# 202011AWSNP04.net
KiCad netlist of a schematic drawn in Altium Designer
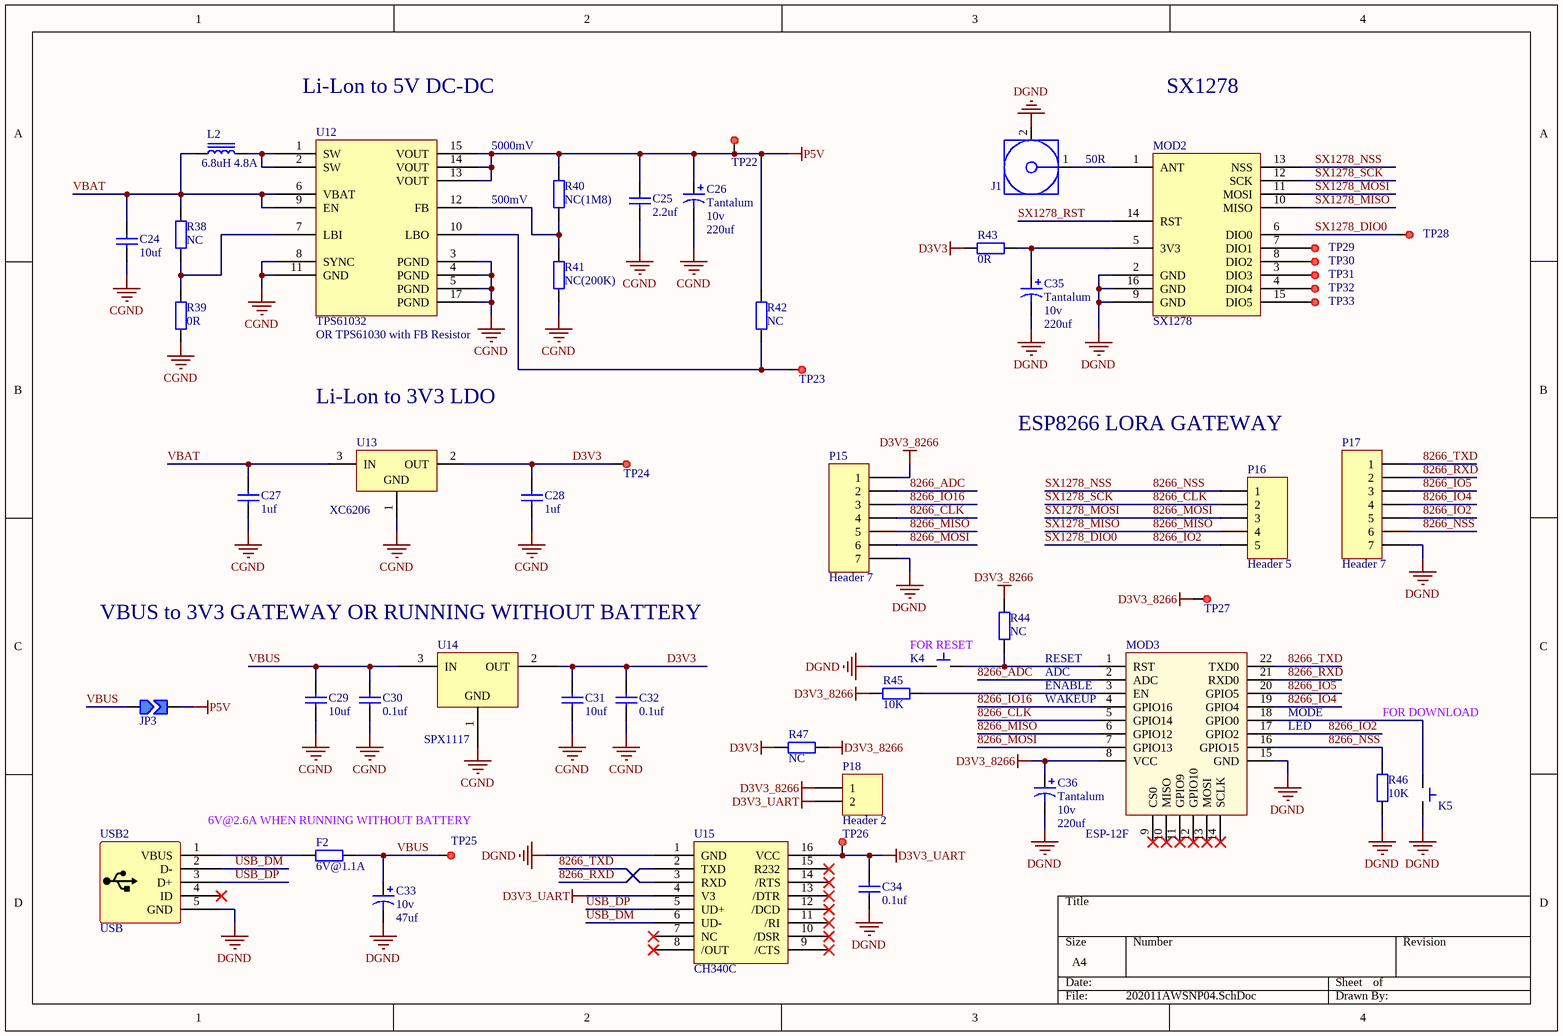
[diagram p0: 202011AWSNP04.SchDoc]

(export (version "E")
  (design (tool "Eeschema 10.0.6"))
  (components
    (comp (ref "C24")
      (value "10uf")
      (footprint "C0805")
      (fields (field (name "Comment") "Cap"))
      (libsource (lib "carrot_lib") (part "Cap"))
    )
    (comp (ref "C25")
      (value "2.2uf")
      (footprint "C0805")
      (fields (field (name "Comment") "Cap"))
      (libsource (lib "carrot_lib") (part "Cap"))
    )
    (comp (ref "C26")
      (value "Tantalum")
      (footprint "C2917T-7343D")
      (fields (field (name "VOLTAGE") "10v") (field (name "ALTIUM_VALUE") "220uf"))
      (libsource (lib "carrot_lib") (part "Cap-Tantalum"))
    )
    (comp (ref "C27")
      (value "1uf")
      (footprint "C0805")
      (fields (field (name "Comment") "Cap"))
      (libsource (lib "carrot_lib") (part "Cap"))
    )
    (comp (ref "C28")
      (value "1uf")
      (footprint "C0805")
      (fields (field (name "Comment") "Cap"))
      (libsource (lib "carrot_lib") (part "Cap"))
    )
    (comp (ref "C29")
      (value "10uf")
      (footprint "C0805")
      (fields (field (name "Comment") "Cap"))
      (libsource (lib "carrot_lib") (part "Cap"))
    )
    (comp (ref "C30")
      (value "0.1uf")
      (footprint "C0805")
      (fields (field (name "Comment") "Cap"))
      (libsource (lib "carrot_lib") (part "Cap"))
    )
    (comp (ref "C31")
      (value "10uf")
      (footprint "C0805")
      (fields (field (name "Comment") "Cap"))
      (libsource (lib "carrot_lib") (part "Cap"))
    )
    (comp (ref "C32")
      (value "0.1uf")
      (footprint "C0805")
      (fields (field (name "Comment") "Cap"))
      (libsource (lib "carrot_lib") (part "Cap"))
    )
    (comp (ref "C33")
      (value "47uf")
      (footprint "C4X5.4-SMD")
      (fields (field (name "VOLTAGE") "10v") (field (name "Comment") "Cap2"))
      (libsource (lib "carrot_lib") (part "Cap2"))
    )
    (comp (ref "C34")
      (value "0.1uf")
      (footprint "C0805")
      (fields (field (name "Comment") "Cap"))
      (libsource (lib "carrot_lib") (part "Cap"))
    )
    (comp (ref "C35")
      (value "Tantalum")
      (footprint "C2917T-7343D")
      (fields (field (name "VOLTAGE") "10v") (field (name "ALTIUM_VALUE") "220uf"))
      (libsource (lib "carrot_lib") (part "Cap-Tantalum"))
    )
    (comp (ref "C36")
      (value "Tantalum")
      (footprint "C2917T-7343D")
      (fields (field (name "VOLTAGE") "10v") (field (name "ALTIUM_VALUE") "220uf"))
      (libsource (lib "carrot_lib") (part "Cap-Tantalum"))
    )
    (comp (ref "F2")
      (value "6V@1.1A")
      (footprint "F1812")
      (fields (field (name "Comment") "Fuse"))
      (libsource (lib "carrot_lib") (part "Fuse"))
    )
    (comp (ref "J1") (value "SMA") (footprint "SMA-3") (libsource (lib "carrot_lib") (part "SMA")))
    (comp (ref "JP3") (value "Jumper") (footprint "Jumper-2") (libsource (lib "carrot_lib") (part "Jumper")))
    (comp (ref "K4")
      (value "Button")
      (footprint "Button-SMT-Small")
      (description "轻触开关")
      (libsource (lib "carrot_lib") (part "Button"))
    )
    (comp (ref "K5")
      (value "Button")
      (footprint "Button-SMT-Small")
      (description "轻触开关")
      (libsource (lib "carrot_lib") (part "Button"))
    )
    (comp (ref "L2")
      (value "6.8uH 4.8A")
      (footprint "L10104")
      (description "Magnetic-Core Inductor")
      (fields (field (name "Comment") "Inductor Iron"))
      (libsource (lib "carrot_lib") (part "Inductor Iron"))
    )
    (comp (ref "MOD2")
      (value "SX1278")
      (footprint "MODULE SX1278")
      (libsource (lib "carrot_lib") (part "Module SX1278"))
    )
    (comp (ref "MOD3")
      (value "ESP-12F")
      (footprint "MODULE ESP-12F")
      (libsource (lib "carrot_lib") (part "Module ESP-12F"))
    )
    (comp (ref "P15")
      (value "Header 7")
      (footprint "HDR1X7")
      (description "Header, 7-Pin")
      (fields (field (name "PUBLISHER") "Altium Limited"))
      (libsource (lib "Miscellaneous Connectors") (part "Header 7"))
    )
    (comp (ref "P16")
      (value "Header 5")
      (footprint "HDR1X5")
      (description "Header, 5-Pin")
      (fields (field (name "PUBLISHER") "Altium Limited"))
      (libsource (lib "Miscellaneous Connectors") (part "Header 5"))
    )
    (comp (ref "P17")
      (value "Header 7")
      (footprint "HDR1X7")
      (description "Header, 7-Pin")
      (fields (field (name "PUBLISHER") "Altium Limited"))
      (libsource (lib "Miscellaneous Connectors") (part "Header 7"))
    )
    (comp (ref "P18")
      (value "Header 2")
      (footprint "HDR1X2")
      (description "Header, 2-Pin")
      (fields (field (name "PUBLISHER") "Altium Limited"))
      (libsource (lib "Miscellaneous Connectors") (part "Header 2"))
    )
    (comp (ref "R38")
      (value "NC")
      (footprint "R0805")
      (description "电阻")
      (fields (field (name "Comment") "Res"))
      (libsource (lib "") (part "Res_3"))
    )
    (comp (ref "R39")
      (value "0R")
      (footprint "R0805")
      (description "电阻")
      (fields (field (name "Comment") "Res"))
      (libsource (lib "") (part "Res_3"))
    )
    (comp (ref "R40")
      (value "NC(1M8)")
      (footprint "R0805")
      (description "电阻")
      (fields (field (name "Comment") "Res"))
      (libsource (lib "") (part "Res_3"))
    )
    (comp (ref "R41")
      (value "NC(200K)")
      (footprint "R0805")
      (description "电阻")
      (fields (field (name "Comment") "Res"))
      (libsource (lib "") (part "Res_3"))
    )
    (comp (ref "R42")
      (value "NC")
      (footprint "R0805")
      (description "电阻")
      (fields (field (name "Comment") "Res"))
      (libsource (lib "") (part "Res_3"))
    )
    (comp (ref "R43")
      (value "0R")
      (footprint "R0805")
      (description "电阻")
      (fields (field (name "Comment") "Res"))
      (libsource (lib "") (part "Res_2"))
    )
    (comp (ref "R44")
      (value "NC")
      (footprint "R0805")
      (description "电阻")
      (fields (field (name "Comment") "Res"))
      (libsource (lib "") (part "Res_3"))
    )
    (comp (ref "R45")
      (value "10K")
      (footprint "R0805")
      (description "电阻")
      (fields (field (name "Comment") "Res"))
      (libsource (lib "") (part "Res_1"))
    )
    (comp (ref "R46")
      (value "10K")
      (footprint "R0805")
      (description "电阻")
      (fields (field (name "Comment") "Res"))
      (libsource (lib "carrot_lib") (part "Res"))
    )
    (comp (ref "R47")
      (value "NC")
      (footprint "R0805")
      (description "电阻")
      (fields (field (name "Comment") "Res"))
      (libsource (lib "") (part "Res_1"))
    )
    (comp (ref "TP22")
      (value "TestPoint")
      (footprint "TestPoint-R30")
      (description "测试点")
      (libsource (lib "carrot_lib") (part "TestPoint"))
    )
    (comp (ref "TP23")
      (value "TestPoint")
      (footprint "TestPoint-R30")
      (description "测试点")
      (libsource (lib "carrot_lib") (part "TestPoint"))
    )
    (comp (ref "TP24")
      (value "TestPoint")
      (footprint "TestPoint-R30")
      (description "测试点")
      (libsource (lib "carrot_lib") (part "TestPoint"))
    )
    (comp (ref "TP25")
      (value "TestPoint")
      (footprint "TestPoint-R30")
      (description "测试点")
      (libsource (lib "carrot_lib") (part "TestPoint"))
    )
    (comp (ref "TP26")
      (value "TestPoint")
      (footprint "TestPoint-R30")
      (description "测试点")
      (libsource (lib "carrot_lib") (part "TestPoint"))
    )
    (comp (ref "TP27")
      (value "TestPoint")
      (footprint "TestPoint-R30")
      (description "测试点")
      (libsource (lib "carrot_lib") (part "TestPoint"))
    )
    (comp (ref "TP28")
      (value "TestPoint")
      (footprint "TestPoint-R30")
      (description "测试点")
      (libsource (lib "carrot_lib") (part "TestPoint"))
    )
    (comp (ref "TP29")
      (value "TestPoint")
      (footprint "TestPoint-R30")
      (description "测试点")
      (libsource (lib "carrot_lib") (part "TestPoint"))
    )
    (comp (ref "TP30")
      (value "TestPoint")
      (footprint "TestPoint-R30")
      (description "测试点")
      (libsource (lib "carrot_lib") (part "TestPoint"))
    )
    (comp (ref "TP31")
      (value "TestPoint")
      (footprint "TestPoint-R30")
      (description "测试点")
      (libsource (lib "carrot_lib") (part "TestPoint"))
    )
    (comp (ref "TP32")
      (value "TestPoint")
      (footprint "TestPoint-R30")
      (description "测试点")
      (libsource (lib "carrot_lib") (part "TestPoint"))
    )
    (comp (ref "TP33")
      (value "TestPoint")
      (footprint "TestPoint-R30")
      (description "测试点")
      (libsource (lib "carrot_lib") (part "TestPoint"))
    )
    (comp (ref "U12")
      (value "TPS61032")
      (footprint "TPS61030-TSSOP16")
      (description "TPS6103x 96% Efficient Synchronous Boost Converter With 4A Switch")
      (libsource (lib "carrot_lib") (part "TPS61032PWP"))
    )
    (comp (ref "U13")
      (value "XC6206")
      (footprint "XC6206-SOT23")
      (description "Low ESR Cap. Compatible Positive Voltage Regulators")
      (libsource (lib "carrot_lib") (part "XC6206"))
    )
    (comp (ref "U14")
      (value "SPX1117")
      (footprint "SPX1117-SOT223")
      (description "800mA Low Dropout Voltage Regulator")
      (libsource (lib "carrot_lib") (part "SPX1117"))
    )
    (comp (ref "U15")
      (value "CH340C")
      (footprint "CH340C-SOP16")
      (description "USB 转串口芯片")
      (libsource (lib "carrot_lib") (part "CH340C"))
    )
    (comp (ref "USB2") (value "USB") (footprint "USB-Mini-SMT") (libsource (lib "carrot_lib") (part "USB")))
  )
  (nets
    (net (code "1") (name "/8266_ADC") (class "Default")
      (node (ref "MOD3") (pin "2") (pinfunction "ADC_2") (pintype "passive"))
      (node (ref "P15") (pin "2") (pinfunction "2_2") (pintype "passive"))
    )
    (net (code "2") (name "/8266_CLK") (class "Default")
      (node (ref "MOD2") (pin "12") (pinfunction "SCK_12") (pintype "passive"))
      (node (ref "MOD3") (pin "5") (pinfunction "GPIO14_5") (pintype "passive"))
      (node (ref "P15") (pin "4") (pinfunction "4_4") (pintype "passive"))
      (node (ref "P16") (pin "2") (pinfunction "2_2") (pintype "passive"))
    )
    (net (code "3") (name "/8266_IO2") (class "Default")
      (node (ref "MOD2") (pin "6") (pinfunction "DIO0_6") (pintype "passive"))
      (node (ref "MOD3") (pin "17") (pinfunction "GPIO2_17") (pintype "passive"))
      (node (ref "P16") (pin "5") (pinfunction "5_5") (pintype "passive"))
      (node (ref "P17") (pin "5") (pinfunction "5_5") (pintype "passive"))
      (node (ref "TP28") (pin "1") (pinfunction "1_1") (pintype "passive"))
    )
    (net (code "4") (name "/8266_IO4") (class "Default")
      (node (ref "MOD3") (pin "19") (pinfunction "GPIO4_19") (pintype "passive"))
      (node (ref "P17") (pin "4") (pinfunction "4_4") (pintype "passive"))
    )
    (net (code "5") (name "/8266_IO5") (class "Default")
      (node (ref "MOD3") (pin "20") (pinfunction "GPIO5_20") (pintype "passive"))
      (node (ref "P17") (pin "3") (pinfunction "3_3") (pintype "passive"))
    )
    (net (code "6") (name "/8266_IO16") (class "Default")
      (node (ref "MOD3") (pin "4") (pinfunction "GPIO16_4") (pintype "passive"))
      (node (ref "P15") (pin "3") (pinfunction "3_3") (pintype "passive"))
    )
    (net (code "7") (name "/8266_MISO") (class "Default")
      (node (ref "MOD2") (pin "10") (pinfunction "MISO_10") (pintype "passive"))
      (node (ref "MOD3") (pin "6") (pinfunction "GPIO12_6") (pintype "passive"))
      (node (ref "P15") (pin "5") (pinfunction "5_5") (pintype "passive"))
      (node (ref "P16") (pin "4") (pinfunction "4_4") (pintype "passive"))
    )
    (net (code "8") (name "/8266_MOSI") (class "Default")
      (node (ref "MOD2") (pin "11") (pinfunction "MOSI_11") (pintype "passive"))
      (node (ref "MOD3") (pin "7") (pinfunction "GPIO13_7") (pintype "passive"))
      (node (ref "P15") (pin "6") (pinfunction "6_6") (pintype "passive"))
      (node (ref "P16") (pin "3") (pinfunction "3_3") (pintype "passive"))
    )
    (net (code "9") (name "/8266_NSS") (class "Default")
      (node (ref "MOD2") (pin "13") (pinfunction "NSS_13") (pintype "passive"))
      (node (ref "MOD3") (pin "16") (pinfunction "GPIO15_16") (pintype "passive"))
      (node (ref "P16") (pin "1") (pinfunction "1_1") (pintype "passive"))
      (node (ref "P17") (pin "6") (pinfunction "6_6") (pintype "passive"))
      (node (ref "R46") (pin "2") (pinfunction "2_2") (pintype "passive"))
    )
    (net (code "10") (name "/8266_RXD") (class "Default")
      (node (ref "MOD3") (pin "21") (pinfunction "RXD0_21") (pintype "passive"))
      (node (ref "P17") (pin "2") (pinfunction "2_2") (pintype "passive"))
      (node (ref "U15") (pin "2") (pinfunction "TXD_2") (pintype "passive"))
    )
    (net (code "11") (name "/8266_TXD") (class "Default")
      (node (ref "MOD3") (pin "22") (pinfunction "TXD0_22") (pintype "passive"))
      (node (ref "P17") (pin "1") (pinfunction "1_1") (pintype "passive"))
      (node (ref "U15") (pin "3") (pinfunction "RXD_3") (pintype "passive"))
    )
    (net (code "12") (name "/SX1278_RST") (class "Default")
      (node (ref "MOD2") (pin "14") (pinfunction "RST_14") (pintype "passive"))
    )
    (net (code "13") (name "/USB_DM") (class "Default")
      (node (ref "U15") (pin "6") (pinfunction "UD-_6") (pintype "passive"))
      (node (ref "USB2") (pin "2") (pinfunction "D-_2") (pintype "passive"))
    )
    (net (code "14") (name "/USB_DP") (class "Default")
      (node (ref "U15") (pin "5") (pinfunction "UD+_5") (pintype "passive"))
      (node (ref "USB2") (pin "3") (pinfunction "D+_3") (pintype "passive"))
    )
    (net (code "15") (name "/VBAT") (class "Default")
      (node (ref "C24") (pin "2") (pinfunction "2_2") (pintype "passive"))
      (node (ref "C27") (pin "2") (pinfunction "2_2") (pintype "passive"))
      (node (ref "L2") (pin "1") (pinfunction "1_1") (pintype "passive"))
      (node (ref "R38") (pin "1") (pinfunction "1_1") (pintype "passive"))
      (node (ref "U12") (pin "6") (pinfunction "VBAT_6") (pintype "passive"))
      (node (ref "U12") (pin "9") (pinfunction "EN_9") (pintype "passive"))
      (node (ref "U13") (pin "3") (pinfunction "IN_3") (pintype "passive"))
    )
    (net (code "16") (name "/VBUS") (class "Default")
      (node (ref "C29") (pin "2") (pinfunction "2_2") (pintype "passive"))
      (node (ref "C30") (pin "2") (pinfunction "2_2") (pintype "passive"))
      (node (ref "C33") (pin "1") (pinfunction "1_1") (pintype "passive"))
      (node (ref "F2") (pin "2") (pinfunction "2_2") (pintype "passive"))
      (node (ref "JP3") (pin "1") (pinfunction "1_1") (pintype "passive"))
      (node (ref "TP25") (pin "1") (pinfunction "1_1") (pintype "passive"))
      (node (ref "U14") (pin "3") (pinfunction "IN_3") (pintype "passive"))
    )
    (net (code "17") (name "CGND") (class "Default")
      (node (ref "C24") (pin "1") (pinfunction "1_1") (pintype "passive"))
      (node (ref "C25") (pin "1") (pinfunction "1_1") (pintype "passive"))
      (node (ref "C26") (pin "2") (pinfunction "2_2") (pintype "passive"))
      (node (ref "C27") (pin "1") (pinfunction "1_1") (pintype "passive"))
      (node (ref "C28") (pin "1") (pinfunction "1_1") (pintype "passive"))
      (node (ref "C29") (pin "1") (pinfunction "1_1") (pintype "passive"))
      (node (ref "C30") (pin "1") (pinfunction "1_1") (pintype "passive"))
      (node (ref "C31") (pin "1") (pinfunction "1_1") (pintype "passive"))
      (node (ref "C32") (pin "1") (pinfunction "1_1") (pintype "passive"))
      (node (ref "R39") (pin "2") (pinfunction "2_2") (pintype "passive"))
      (node (ref "R41") (pin "2") (pinfunction "2_2") (pintype "passive"))
      (node (ref "U12") (pin "11") (pinfunction "GND_11") (pintype "passive"))
      (node (ref "U12") (pin "17") (pinfunction "PGND_17") (pintype "passive"))
      (node (ref "U12") (pin "3") (pinfunction "PGND_3") (pintype "passive"))
      (node (ref "U12") (pin "4") (pinfunction "PGND_4") (pintype "passive"))
      (node (ref "U12") (pin "5") (pinfunction "PGND_5") (pintype "passive"))
      (node (ref "U12") (pin "8") (pinfunction "SYNC_8") (pintype "passive"))
      (node (ref "U13") (pin "1") (pinfunction "GND_1") (pintype "passive"))
      (node (ref "U14") (pin "1") (pinfunction "GND_1") (pintype "passive"))
    )
    (net (code "18") (name "D3V3") (class "Default")
      (node (ref "C28") (pin "2") (pinfunction "2_2") (pintype "passive"))
      (node (ref "C31") (pin "2") (pinfunction "2_2") (pintype "passive"))
      (node (ref "C32") (pin "2") (pinfunction "2_2") (pintype "passive"))
      (node (ref "R43") (pin "2") (pinfunction "2_2") (pintype "passive"))
      (node (ref "R47") (pin "1") (pinfunction "1_1") (pintype "passive"))
      (node (ref "TP24") (pin "1") (pinfunction "1_1") (pintype "passive"))
      (node (ref "U13") (pin "2") (pinfunction "OUT_2") (pintype "passive"))
      (node (ref "U14") (pin "2") (pinfunction "OUT_2") (pintype "passive"))
    )
    (net (code "19") (name "D3V3_8266") (class "Default")
      (node (ref "C36") (pin "1") (pinfunction "1_1") (pintype "passive"))
      (node (ref "MOD3") (pin "8") (pinfunction "VCC_8") (pintype "passive"))
      (node (ref "P15") (pin "1") (pinfunction "1_1") (pintype "passive"))
      (node (ref "P18") (pin "1") (pinfunction "1_1") (pintype "passive"))
      (node (ref "R44") (pin "1") (pinfunction "1_1") (pintype "passive"))
      (node (ref "R45") (pin "1") (pinfunction "1_1") (pintype "passive"))
      (node (ref "R47") (pin "2") (pinfunction "2_2") (pintype "passive"))
      (node (ref "TP27") (pin "1") (pinfunction "1_1") (pintype "passive"))
    )
    (net (code "20") (name "D3V3_UART") (class "Default")
      (node (ref "C34") (pin "1") (pinfunction "1_1") (pintype "passive"))
      (node (ref "P18") (pin "2") (pinfunction "2_2") (pintype "passive"))
      (node (ref "TP26") (pin "1") (pinfunction "1_1") (pintype "passive"))
      (node (ref "U15") (pin "16") (pinfunction "VCC_16") (pintype "passive"))
      (node (ref "U15") (pin "4") (pinfunction "V3_4") (pintype "passive"))
    )
    (net (code "21") (name "DGND") (class "Default")
      (node (ref "C33") (pin "2") (pinfunction "2_2") (pintype "passive"))
      (node (ref "C34") (pin "2") (pinfunction "2_2") (pintype "passive"))
      (node (ref "C35") (pin "2") (pinfunction "2_2") (pintype "passive"))
      (node (ref "C36") (pin "2") (pinfunction "2_2") (pintype "passive"))
      (node (ref "J1") (pin "2") (pinfunction "GND_2") (pintype "power_in"))
      (node (ref "K4") (pin "1") (pinfunction "IN_1") (pintype "passive"))
      (node (ref "K5") (pin "2") (pinfunction "OUT_2") (pintype "passive"))
      (node (ref "MOD2") (pin "16") (pinfunction "GND_16") (pintype "passive"))
      (node (ref "MOD2") (pin "2") (pinfunction "GND_2") (pintype "passive"))
      (node (ref "MOD2") (pin "9") (pinfunction "GND_9") (pintype "passive"))
      (node (ref "MOD3") (pin "15") (pinfunction "GND_15") (pintype "passive"))
      (node (ref "P15") (pin "7") (pinfunction "7_7") (pintype "passive"))
      (node (ref "P17") (pin "7") (pinfunction "7_7") (pintype "passive"))
      (node (ref "R46") (pin "1") (pinfunction "1_1") (pintype "passive"))
      (node (ref "U15") (pin "1") (pinfunction "GND_1") (pintype "passive"))
      (node (ref "USB2") (pin "5") (pinfunction "GND_5") (pintype "passive"))
    )
    (net (code "22") (name "Net-(J1-Signal)") (class "Default")
      (node (ref "J1") (pin "1") (pinfunction "Signal_1") (pintype "power_in"))
      (node (ref "MOD2") (pin "1") (pinfunction "ANT_1") (pintype "passive"))
    )
    (net (code "23") (name "Net-(K4-OUT)") (class "Default")
      (node (ref "K4") (pin "2") (pinfunction "OUT_2") (pintype "passive"))
      (node (ref "MOD3") (pin "1") (pinfunction "RST_1") (pintype "passive"))
      (node (ref "R44") (pin "2") (pinfunction "2_2") (pintype "passive"))
    )
    (net (code "24") (name "Net-(K5-IN)") (class "Default")
      (node (ref "K5") (pin "1") (pinfunction "IN_1") (pintype "passive"))
      (node (ref "MOD3") (pin "18") (pinfunction "GPIO0_18") (pintype "passive"))
    )
    (net (code "25") (name "Net-(L2-Pad2)") (class "Default")
      (node (ref "L2") (pin "2") (pinfunction "2_2") (pintype "passive"))
      (node (ref "U12") (pin "1") (pinfunction "SW_1") (pintype "passive"))
      (node (ref "U12") (pin "2") (pinfunction "SW_2") (pintype "passive"))
    )
    (net (code "26") (name "Net-(MOD2-3V3)") (class "Default")
      (node (ref "C35") (pin "1") (pinfunction "1_1") (pintype "passive"))
      (node (ref "MOD2") (pin "5") (pinfunction "3V3_5") (pintype "passive"))
      (node (ref "R43") (pin "1") (pinfunction "1_1") (pintype "passive"))
    )
    (net (code "27") (name "Net-(MOD2-DIO1)") (class "Default")
      (node (ref "MOD2") (pin "7") (pinfunction "DIO1_7") (pintype "passive"))
      (node (ref "TP29") (pin "1") (pinfunction "1_1") (pintype "passive"))
    )
    (net (code "28") (name "Net-(MOD2-DIO2)") (class "Default")
      (node (ref "MOD2") (pin "8") (pinfunction "DIO2_8") (pintype "passive"))
      (node (ref "TP30") (pin "1") (pinfunction "1_1") (pintype "passive"))
    )
    (net (code "29") (name "Net-(MOD2-DIO3)") (class "Default")
      (node (ref "MOD2") (pin "3") (pinfunction "DIO3_3") (pintype "passive"))
      (node (ref "TP31") (pin "1") (pinfunction "1_1") (pintype "passive"))
    )
    (net (code "30") (name "Net-(MOD2-DIO4)") (class "Default")
      (node (ref "MOD2") (pin "4") (pinfunction "DIO4_4") (pintype "passive"))
      (node (ref "TP32") (pin "1") (pinfunction "1_1") (pintype "passive"))
    )
    (net (code "31") (name "Net-(MOD2-DIO5)") (class "Default")
      (node (ref "MOD2") (pin "15") (pinfunction "DIO5_15") (pintype "passive"))
      (node (ref "TP33") (pin "1") (pinfunction "1_1") (pintype "passive"))
    )
    (net (code "32") (name "Net-(MOD3-EN)") (class "Default")
      (node (ref "MOD3") (pin "3") (pinfunction "EN_3") (pintype "passive"))
      (node (ref "R45") (pin "2") (pinfunction "2_2") (pintype "passive"))
    )
    (net (code "33") (name "Net-(U12-FB)") (class "Default")
      (node (ref "R40") (pin "2") (pinfunction "2_2") (pintype "passive"))
      (node (ref "R41") (pin "1") (pinfunction "1_1") (pintype "passive"))
      (node (ref "U12") (pin "12") (pinfunction "FB_12") (pintype "passive"))
    )
    (net (code "34") (name "Net-(U12-LBI)") (class "Default")
      (node (ref "R38") (pin "2") (pinfunction "2_2") (pintype "passive"))
      (node (ref "R39") (pin "1") (pinfunction "1_1") (pintype "passive"))
      (node (ref "U12") (pin "7") (pinfunction "LBI_7") (pintype "passive"))
    )
    (net (code "35") (name "Net-(U12-LBO)") (class "Default")
      (node (ref "R42") (pin "2") (pinfunction "2_2") (pintype "passive"))
      (node (ref "TP23") (pin "1") (pinfunction "1_1") (pintype "passive"))
      (node (ref "U12") (pin "10") (pinfunction "LBO_10") (pintype "passive"))
    )
    (net (code "36") (name "Net-(USB2-VBUS)") (class "Default")
      (node (ref "F2") (pin "1") (pinfunction "1_1") (pintype "passive"))
      (node (ref "USB2") (pin "1") (pinfunction "VBUS_1") (pintype "passive"))
    )
    (net (code "37") (name "P5V") (class "Default")
      (node (ref "C25") (pin "2") (pinfunction "2_2") (pintype "passive"))
      (node (ref "C26") (pin "1") (pinfunction "1_1") (pintype "passive"))
      (node (ref "JP3") (pin "2") (pinfunction "2_2") (pintype "passive"))
      (node (ref "R40") (pin "1") (pinfunction "1_1") (pintype "passive"))
      (node (ref "R42") (pin "1") (pinfunction "1_1") (pintype "passive"))
      (node (ref "TP22") (pin "1") (pinfunction "1_1") (pintype "passive"))
      (node (ref "U12") (pin "13") (pinfunction "VOUT_13") (pintype "passive"))
      (node (ref "U12") (pin "14") (pinfunction "VOUT_14") (pintype "passive"))
      (node (ref "U12") (pin "15") (pinfunction "VOUT_15") (pintype "passive"))
    )
    (net (code "38") (name "unconnected-(MOD3-CS0-Pad9)") (class "Default")
      (node (ref "MOD3") (pin "9") (pinfunction "CS0_9") (pintype "passive+no_connect"))
    )
    (net (code "39") (name "unconnected-(MOD3-GPIO9-Pad11)") (class "Default")
      (node (ref "MOD3") (pin "11") (pinfunction "GPIO9_11") (pintype "passive+no_connect"))
    )
    (net (code "40") (name "unconnected-(MOD3-GPIO10-Pad12)") (class "Default")
      (node (ref "MOD3") (pin "12") (pinfunction "GPIO10_12") (pintype "passive+no_connect"))
    )
    (net (code "41") (name "unconnected-(MOD3-MISO-Pad10)") (class "Default")
      (node (ref "MOD3") (pin "10") (pinfunction "MISO_10") (pintype "passive+no_connect"))
    )
    (net (code "42") (name "unconnected-(MOD3-MOSI-Pad13)") (class "Default")
      (node (ref "MOD3") (pin "13") (pinfunction "MOSI_13") (pintype "passive+no_connect"))
    )
    (net (code "43") (name "unconnected-(MOD3-SCLK-Pad14)") (class "Default")
      (node (ref "MOD3") (pin "14") (pinfunction "SCLK_14") (pintype "passive+no_connect"))
    )
    (net (code "44") (name "unconnected-(U15-NC-Pad7)") (class "Default")
      (node (ref "U15") (pin "7") (pinfunction "NC_7") (pintype "passive+no_connect"))
    )
    (net (code "45") (name "unconnected-(U15-R232-Pad15)") (class "Default")
      (node (ref "U15") (pin "15") (pinfunction "R232_15") (pintype "passive+no_connect"))
    )
    (net (code "46") (name "unconnected-(U15-{slash}CTS-Pad9)") (class "Default")
      (node (ref "U15") (pin "9") (pinfunction "/CTS_9") (pintype "passive+no_connect"))
    )
    (net (code "47") (name "unconnected-(U15-{slash}DCD-Pad12)") (class "Default")
      (node (ref "U15") (pin "12") (pinfunction "/DCD_12") (pintype "passive+no_connect"))
    )
    (net (code "48") (name "unconnected-(U15-{slash}DSR-Pad10)") (class "Default")
      (node (ref "U15") (pin "10") (pinfunction "/DSR_10") (pintype "passive+no_connect"))
    )
    (net (code "49") (name "unconnected-(U15-{slash}DTR-Pad13)") (class "Default")
      (node (ref "U15") (pin "13") (pinfunction "/DTR_13") (pintype "passive+no_connect"))
    )
    (net (code "50") (name "unconnected-(U15-{slash}OUT-Pad8)") (class "Default")
      (node (ref "U15") (pin "8") (pinfunction "/OUT_8") (pintype "passive+no_connect"))
    )
    (net (code "51") (name "unconnected-(U15-{slash}RI-Pad11)") (class "Default")
      (node (ref "U15") (pin "11") (pinfunction "/RI_11") (pintype "passive+no_connect"))
    )
    (net (code "52") (name "unconnected-(U15-{slash}RTS-Pad14)") (class "Default")
      (node (ref "U15") (pin "14") (pinfunction "/RTS_14") (pintype "passive+no_connect"))
    )
    (net (code "53") (name "unconnected-(USB2-ID-Pad4)") (class "Default")
      (node (ref "USB2") (pin "4") (pinfunction "ID_4") (pintype "passive+no_connect"))
    )
  )
)
